# SCH_Vansh_2023-10-03.net
KiCad netlist of a schematic drawn in EasyEDA
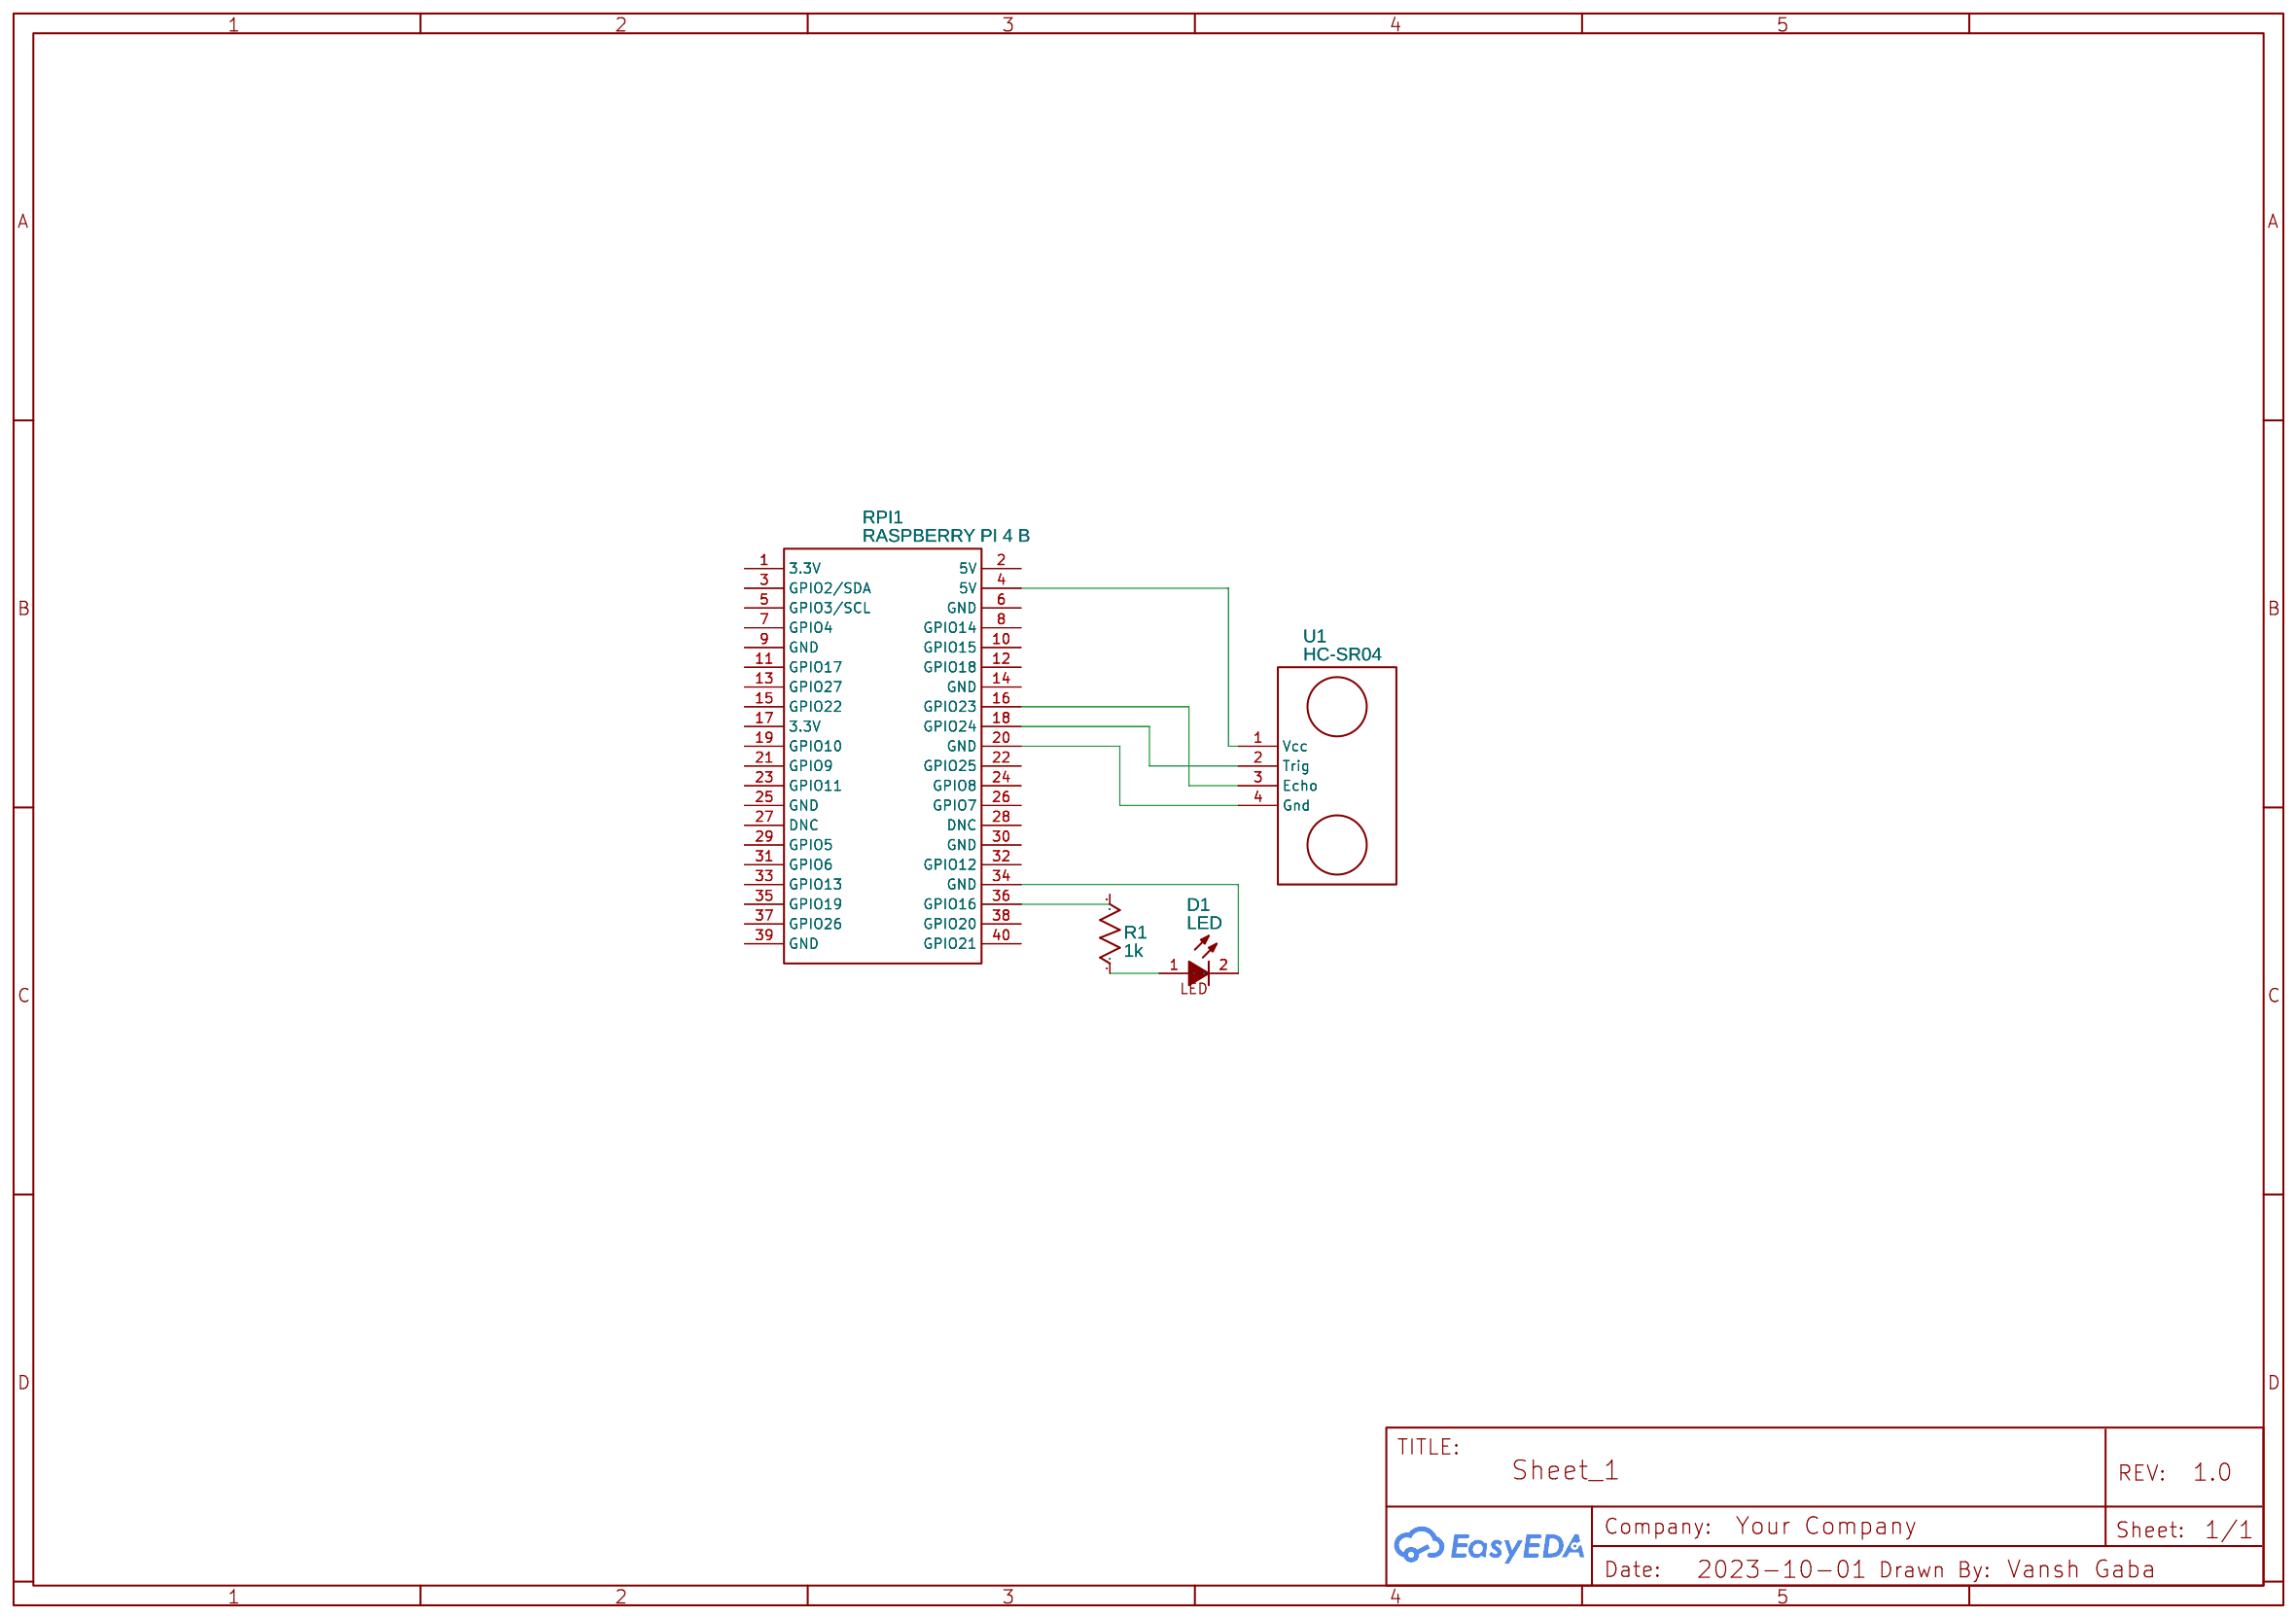
[diagram p0: schematic sheet]

(export (version "E")
  (design (tool "Eeschema 10.0.6"))
  (components
    (comp (ref "D1")
      (value "LED")
      (fields (field (name "Manufacturer Part") "5600") (field (name "Manufacturer") "VccLite"))
      (libsource (lib "") (part "LED"))
    )
    (comp (ref "R1") (value "1k") (libsource (lib "") (part "R_0603_US")))
    (comp (ref "RPI1")
      (value "RASPBERRY PI 4 B")
      (fields
        (field (name "Manufacturer Part") "Raspberry Pi 3 - Model B+ - 1.4GHz Cortex-A53 with 1GB RAM")
        (field (name "Manufacturer") "Raspberry Pi")
      )
      (libsource (lib "") (part "RASPBERRY PI 3 B+"))
    )
    (comp (ref "U1") (value "HC-SR04") (libsource (lib "") (part "HC-SR04")))
  )
  (nets
    (net (code "1") (name "Net-(D1-A)") (class "Default")
      (node (ref "D1") (pin "1") (pinfunction "A_1") (pintype "input"))
      (node (ref "R1") (pin "1") (pinfunction "1_1") (pintype "unspecified"))
    )
    (net (code "2") (name "Net-(D1-K)") (class "Default")
      (node (ref "D1") (pin "2") (pinfunction "K_2") (pintype "input"))
      (node (ref "RPI1") (pin "34") (pinfunction "GND_34") (pintype "unspecified"))
    )
    (net (code "3") (name "Net-(RPI1-GPIO16)") (class "Default")
      (node (ref "R1") (pin "2") (pinfunction "2_2") (pintype "unspecified"))
      (node (ref "RPI1") (pin "36") (pinfunction "GPIO16_36") (pintype "unspecified"))
    )
    (net (code "4") (name "Net-(RPI1-GPIO23)") (class "Default")
      (node (ref "RPI1") (pin "16") (pinfunction "GPIO23_16") (pintype "unspecified"))
      (node (ref "U1") (pin "3") (pinfunction "Echo_3") (pintype "unspecified"))
    )
    (net (code "5") (name "Net-(RPI1-GPIO24)") (class "Default")
      (node (ref "RPI1") (pin "18") (pinfunction "GPIO24_18") (pintype "unspecified"))
      (node (ref "U1") (pin "2") (pinfunction "Trig_2") (pintype "unspecified"))
    )
    (net (code "6") (name "Net-(U1-Gnd)") (class "Default")
      (node (ref "RPI1") (pin "20") (pinfunction "GND_20") (pintype "unspecified"))
      (node (ref "U1") (pin "4") (pinfunction "Gnd_4") (pintype "unspecified"))
    )
    (net (code "7") (name "Net-(U1-Vcc)") (class "Default")
      (node (ref "RPI1") (pin "4") (pinfunction "5V_4") (pintype "unspecified"))
      (node (ref "U1") (pin "1") (pinfunction "Vcc_1") (pintype "unspecified"))
    )
    (net (code "8") (name "unconnected-(RPI1-3.3V-Pad1)") (class "Default")
      (node (ref "RPI1") (pin "1") (pinfunction "3.3V_1") (pintype "unspecified"))
    )
    (net (code "9") (name "unconnected-(RPI1-3.3V-Pad17)") (class "Default")
      (node (ref "RPI1") (pin "17") (pinfunction "3.3V_17") (pintype "unspecified"))
    )
    (net (code "10") (name "unconnected-(RPI1-5V-Pad2)") (class "Default")
      (node (ref "RPI1") (pin "2") (pinfunction "5V_2") (pintype "unspecified"))
    )
    (net (code "11") (name "unconnected-(RPI1-DNC-Pad27)") (class "Default")
      (node (ref "RPI1") (pin "27") (pinfunction "DNC_27") (pintype "unspecified"))
    )
    (net (code "12") (name "unconnected-(RPI1-DNC-Pad28)") (class "Default")
      (node (ref "RPI1") (pin "28") (pinfunction "DNC_28") (pintype "unspecified"))
    )
    (net (code "13") (name "unconnected-(RPI1-GND-Pad6)") (class "Default")
      (node (ref "RPI1") (pin "6") (pinfunction "GND_6") (pintype "unspecified"))
    )
    (net (code "14") (name "unconnected-(RPI1-GND-Pad9)") (class "Default")
      (node (ref "RPI1") (pin "9") (pinfunction "GND_9") (pintype "unspecified"))
    )
    (net (code "15") (name "unconnected-(RPI1-GND-Pad14)") (class "Default")
      (node (ref "RPI1") (pin "14") (pinfunction "GND_14") (pintype "unspecified"))
    )
    (net (code "16") (name "unconnected-(RPI1-GND-Pad25)") (class "Default")
      (node (ref "RPI1") (pin "25") (pinfunction "GND_25") (pintype "unspecified"))
    )
    (net (code "17") (name "unconnected-(RPI1-GND-Pad30)") (class "Default")
      (node (ref "RPI1") (pin "30") (pinfunction "GND_30") (pintype "unspecified"))
    )
    (net (code "18") (name "unconnected-(RPI1-GND-Pad39)") (class "Default")
      (node (ref "RPI1") (pin "39") (pinfunction "GND_39") (pintype "unspecified"))
    )
    (net (code "19") (name "unconnected-(RPI1-GPIO2{slash}SDA-Pad3)") (class "Default")
      (node (ref "RPI1") (pin "3") (pinfunction "GPIO2/SDA_3") (pintype "unspecified"))
    )
    (net (code "20") (name "unconnected-(RPI1-GPIO3{slash}SCL-Pad5)") (class "Default")
      (node (ref "RPI1") (pin "5") (pinfunction "GPIO3/SCL_5") (pintype "unspecified"))
    )
    (net (code "21") (name "unconnected-(RPI1-GPIO4-Pad7)") (class "Default")
      (node (ref "RPI1") (pin "7") (pinfunction "GPIO4_7") (pintype "unspecified"))
    )
    (net (code "22") (name "unconnected-(RPI1-GPIO5-Pad29)") (class "Default")
      (node (ref "RPI1") (pin "29") (pinfunction "GPIO5_29") (pintype "unspecified"))
    )
    (net (code "23") (name "unconnected-(RPI1-GPIO6-Pad31)") (class "Default")
      (node (ref "RPI1") (pin "31") (pinfunction "GPIO6_31") (pintype "unspecified"))
    )
    (net (code "24") (name "unconnected-(RPI1-GPIO7-Pad26)") (class "Default")
      (node (ref "RPI1") (pin "26") (pinfunction "GPIO7_26") (pintype "unspecified"))
    )
    (net (code "25") (name "unconnected-(RPI1-GPIO8-Pad24)") (class "Default")
      (node (ref "RPI1") (pin "24") (pinfunction "GPIO8_24") (pintype "unspecified"))
    )
    (net (code "26") (name "unconnected-(RPI1-GPIO9-Pad21)") (class "Default")
      (node (ref "RPI1") (pin "21") (pinfunction "GPIO9_21") (pintype "unspecified"))
    )
    (net (code "27") (name "unconnected-(RPI1-GPIO10-Pad19)") (class "Default")
      (node (ref "RPI1") (pin "19") (pinfunction "GPIO10_19") (pintype "unspecified"))
    )
    (net (code "28") (name "unconnected-(RPI1-GPIO11-Pad23)") (class "Default")
      (node (ref "RPI1") (pin "23") (pinfunction "GPIO11_23") (pintype "unspecified"))
    )
    (net (code "29") (name "unconnected-(RPI1-GPIO12-Pad32)") (class "Default")
      (node (ref "RPI1") (pin "32") (pinfunction "GPIO12_32") (pintype "unspecified"))
    )
    (net (code "30") (name "unconnected-(RPI1-GPIO13-Pad33)") (class "Default")
      (node (ref "RPI1") (pin "33") (pinfunction "GPIO13_33") (pintype "unspecified"))
    )
    (net (code "31") (name "unconnected-(RPI1-GPIO14-Pad8)") (class "Default")
      (node (ref "RPI1") (pin "8") (pinfunction "GPIO14_8") (pintype "unspecified"))
    )
    (net (code "32") (name "unconnected-(RPI1-GPIO15-Pad10)") (class "Default")
      (node (ref "RPI1") (pin "10") (pinfunction "GPIO15_10") (pintype "unspecified"))
    )
    (net (code "33") (name "unconnected-(RPI1-GPIO17-Pad11)") (class "Default")
      (node (ref "RPI1") (pin "11") (pinfunction "GPIO17_11") (pintype "unspecified"))
    )
    (net (code "34") (name "unconnected-(RPI1-GPIO18-Pad12)") (class "Default")
      (node (ref "RPI1") (pin "12") (pinfunction "GPIO18_12") (pintype "unspecified"))
    )
    (net (code "35") (name "unconnected-(RPI1-GPIO19-Pad35)") (class "Default")
      (node (ref "RPI1") (pin "35") (pinfunction "GPIO19_35") (pintype "unspecified"))
    )
    (net (code "36") (name "unconnected-(RPI1-GPIO20-Pad38)") (class "Default")
      (node (ref "RPI1") (pin "38") (pinfunction "GPIO20_38") (pintype "unspecified"))
    )
    (net (code "37") (name "unconnected-(RPI1-GPIO21-Pad40)") (class "Default")
      (node (ref "RPI1") (pin "40") (pinfunction "GPIO21_40") (pintype "unspecified"))
    )
    (net (code "38") (name "unconnected-(RPI1-GPIO22-Pad15)") (class "Default")
      (node (ref "RPI1") (pin "15") (pinfunction "GPIO22_15") (pintype "unspecified"))
    )
    (net (code "39") (name "unconnected-(RPI1-GPIO25-Pad22)") (class "Default")
      (node (ref "RPI1") (pin "22") (pinfunction "GPIO25_22") (pintype "unspecified"))
    )
    (net (code "40") (name "unconnected-(RPI1-GPIO26-Pad37)") (class "Default")
      (node (ref "RPI1") (pin "37") (pinfunction "GPIO26_37") (pintype "unspecified"))
    )
    (net (code "41") (name "unconnected-(RPI1-GPIO27-Pad13)") (class "Default")
      (node (ref "RPI1") (pin "13") (pinfunction "GPIO27_13") (pintype "unspecified"))
    )
  )
)
